# Custom_Sheild-PCB.net
KiCad netlist of a schematic drawn in EAGLE
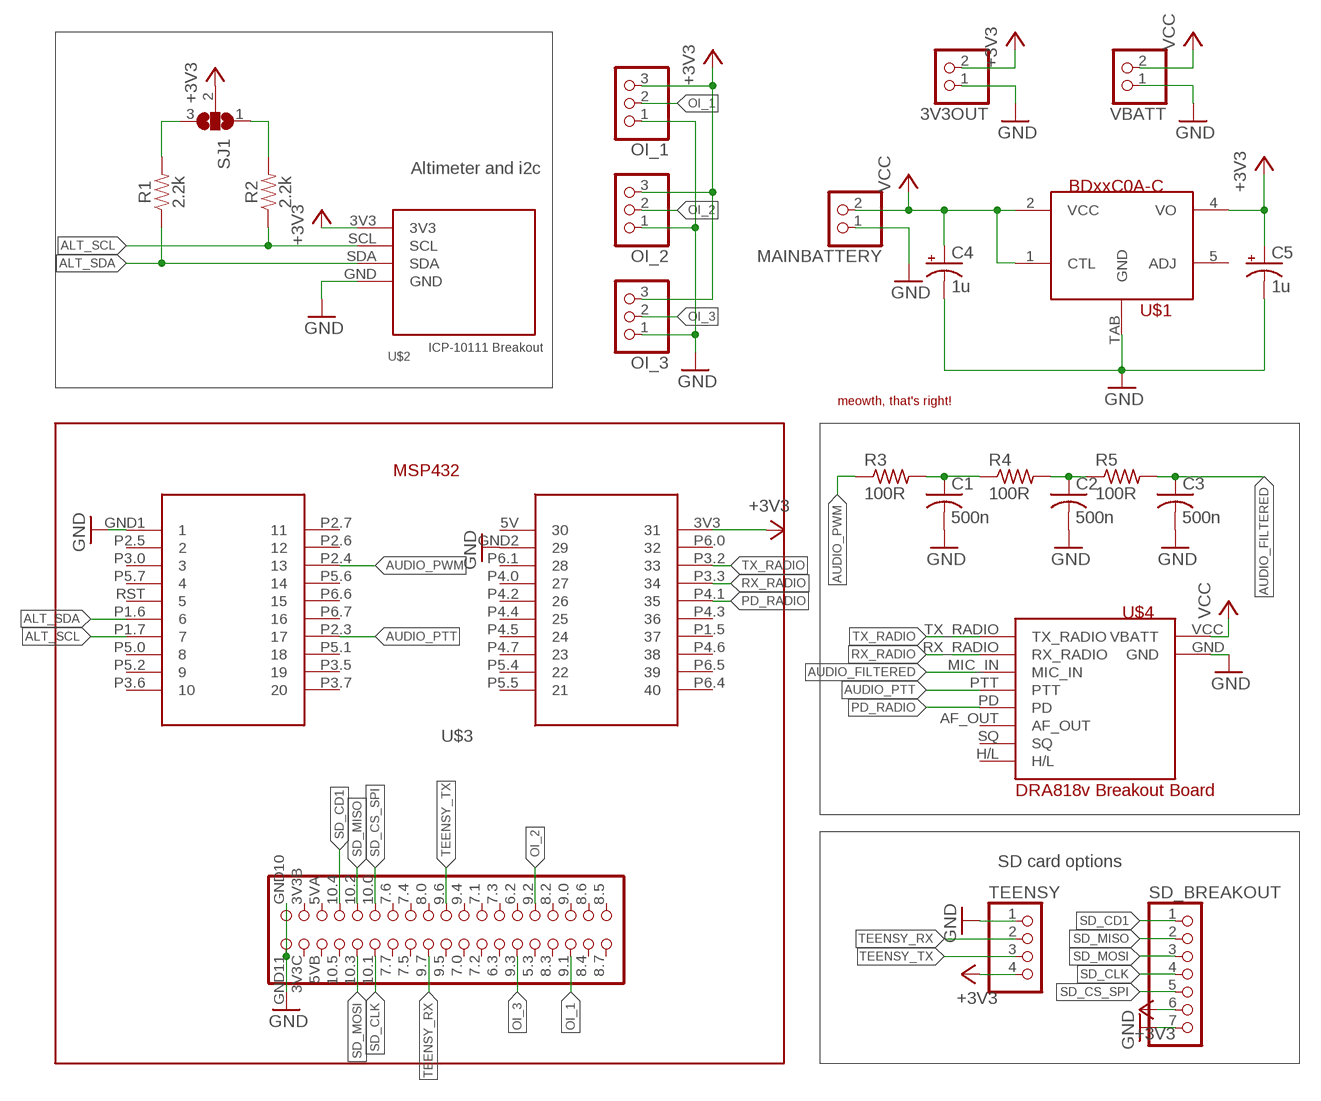
[diagram p0: schematic, sheet 1]

(export (version "E")
  (design (tool "Eeschema 10.0.6"))
  (components
    (comp (ref "3V3OUT")
      (value "PINHD-1X2")
      (footprint "eagle-import:1X02")
      (libsource (lib "eagle-import") (part "PINHD-1X2"))
    )
    (comp (ref "C1")
      (value "500n")
      (footprint "eagle-import:C0805")
      (libsource (lib "eagle-import") (part "C-USC0805"))
    )
    (comp (ref "C2")
      (value "500n")
      (footprint "eagle-import:C0805")
      (libsource (lib "eagle-import") (part "C-USC0805"))
    )
    (comp (ref "C3")
      (value "500n")
      (footprint "eagle-import:C0805")
      (libsource (lib "eagle-import") (part "C-USC0805"))
    )
    (comp (ref "C4")
      (value "1u")
      (footprint "eagle-import:PANASONIC_A")
      (libsource (lib "eagle-import") (part "CPOL-USA"))
    )
    (comp (ref "C5")
      (value "1u")
      (footprint "eagle-import:PANASONIC_A")
      (libsource (lib "eagle-import") (part "CPOL-USA"))
    )
    (comp (ref "MAINBATTERY")
      (value "PINHD-1X2")
      (footprint "eagle-import:1X02")
      (libsource (lib "eagle-import") (part "PINHD-1X2"))
    )
    (comp (ref "OI_1")
      (value "PINHD-1X3")
      (footprint "eagle-import:1X03")
      (libsource (lib "eagle-import") (part "PINHD-1X3"))
    )
    (comp (ref "OI_2")
      (value "PINHD-1X3")
      (footprint "eagle-import:1X03")
      (libsource (lib "eagle-import") (part "PINHD-1X3"))
    )
    (comp (ref "OI_3")
      (value "PINHD-1X3")
      (footprint "eagle-import:1X03")
      (libsource (lib "eagle-import") (part "PINHD-1X3"))
    )
    (comp (ref "R1")
      (value "2.2k")
      (footprint "eagle-import:0603")
      (libsource (lib "eagle-import") (part "2.2KOHM-0603-1/10W-1%"))
    )
    (comp (ref "R2")
      (value "2.2k")
      (footprint "eagle-import:0603")
      (libsource (lib "eagle-import") (part "2.2KOHM-0603-1/10W-1%"))
    )
    (comp (ref "R3")
      (value "100R")
      (footprint "eagle-import:R0805")
      (libsource (lib "eagle-import") (part "R-US_R0805"))
    )
    (comp (ref "R4")
      (value "100R")
      (footprint "eagle-import:R0805")
      (libsource (lib "eagle-import") (part "R-US_R0805"))
    )
    (comp (ref "R5")
      (value "100R")
      (footprint "eagle-import:R0805")
      (libsource (lib "eagle-import") (part "R-US_R0805"))
    )
    (comp (ref "SD_BREAKOUT")
      (value "PINHD-1X7")
      (footprint "eagle-import:1X07")
      (libsource (lib "eagle-import") (part "PINHD-1X7"))
    )
    (comp (ref "SJ1")
      (value "SJ2W")
      (footprint "eagle-import:SJ_2")
      (libsource (lib "eagle-import") (part "SJ2W"))
    )
    (comp (ref "TEENSY")
      (value "PINHD-1X4")
      (footprint "eagle-import:1X04")
      (libsource (lib "eagle-import") (part "PINHD-1X4"))
    )
    (comp (ref "U$1")
      (value "BDXXC0A-CBD33C0AWFP-CE2")
      (footprint "eagle-import:TO252-5-11")
      (libsource (lib "eagle-import") (part "BDXXC0A-CBD33C0AWFP-CE2"))
    )
    (comp (ref "U$2")
      (value "ALTIMETER")
      (footprint "eagle-import:ALTIMETER")
      (libsource (lib "eagle-import") (part "ALTIMETER"))
    )
    (comp (ref "U$3")
      (value "MSP432")
      (footprint "eagle-import:MSP432")
      (libsource (lib "eagle-import") (part "MSP432"))
    )
    (comp (ref "U$4")
      (value "DRA_BREAKOUT")
      (footprint "eagle-import:DRA_BREAKOUT")
      (libsource (lib "eagle-import") (part "DRA_BREAKOUT"))
    )
    (comp (ref "U$5")
      (value "MEOWTH")
      (footprint "eagle-import:MEOWTH")
      (libsource (lib "eagle-import") (part "MEOWTH"))
    )
    (comp (ref "VBATT")
      (value "PINHD-1X2")
      (footprint "eagle-import:1X02")
      (libsource (lib "eagle-import") (part "PINHD-1X2"))
    )
  )
  (nets
    (net (code "1") (name "+3V3") (class "Default")
      (node (ref "3V3OUT") (pin "2") (pinfunction "2_2") (pintype "passive"))
      (node (ref "C5") (pin "+") (pinfunction "+_+") (pintype "passive"))
      (node (ref "OI_1") (pin "3") (pinfunction "3_3") (pintype "passive"))
      (node (ref "OI_2") (pin "3") (pinfunction "3_3") (pintype "passive"))
      (node (ref "OI_3") (pin "3") (pinfunction "3_3") (pintype "passive"))
      (node (ref "SD_BREAKOUT") (pin "6") (pinfunction "6_6") (pintype "passive"))
      (node (ref "SJ1") (pin "2") (pinfunction "2_2") (pintype "passive"))
      (node (ref "TEENSY") (pin "4") (pinfunction "4_4") (pintype "passive"))
      (node (ref "U$1") (pin "4") (pinfunction "VO_4") (pintype "power_in"))
      (node (ref "U$2") (pin "3V3") (pinfunction "3V3_3V3") (pintype "power_in"))
      (node (ref "U$3") (pin "3V3") (pinfunction "31_3V3") (pintype "power_in"))
    )
    (net (code "2") (name "/30") (class "Default")
      (node (ref "U$3") (pin "5V") (pinfunction "30_5V") (pintype "power_in"))
    )
    (net (code "3") (name "ALT_SCL") (class "Default")
      (node (ref "R2") (pin "1") (pinfunction "1_1") (pintype "passive"))
      (node (ref "U$2") (pin "SCL") (pinfunction "SCL_SCL") (pintype "bidirectional"))
      (node (ref "U$3") (pin "P1.7") (pinfunction "7_P1.7") (pintype "bidirectional"))
    )
    (net (code "4") (name "ALT_SDA") (class "Default")
      (node (ref "R1") (pin "1") (pinfunction "1_1") (pintype "passive"))
      (node (ref "U$2") (pin "SDA") (pinfunction "SDA_SDA") (pintype "bidirectional"))
      (node (ref "U$3") (pin "P1.6") (pinfunction "6_P1.6") (pintype "bidirectional"))
    )
    (net (code "5") (name "AUDIO_FILTERED") (class "Default")
      (node (ref "C3") (pin "1") (pinfunction "1_1") (pintype "passive"))
      (node (ref "R5") (pin "2") (pinfunction "2_2") (pintype "passive"))
      (node (ref "U$4") (pin "MIC_IN") (pinfunction "MIC_IN_MIC_IN") (pintype "bidirectional"))
    )
    (net (code "6") (name "AUDIO_PTT") (class "Default")
      (node (ref "U$3") (pin "P2.3") (pinfunction "17_P2.3") (pintype "bidirectional"))
      (node (ref "U$4") (pin "PTT") (pinfunction "PTT_PTT") (pintype "bidirectional"))
    )
    (net (code "7") (name "AUDIO_PWM") (class "Default")
      (node (ref "R3") (pin "1") (pinfunction "1_1") (pintype "passive"))
      (node (ref "U$3") (pin "P2.4") (pinfunction "13_P2.4") (pintype "bidirectional"))
    )
    (net (code "8") (name "GND") (class "Default")
      (node (ref "3V3OUT") (pin "1") (pinfunction "1_1") (pintype "passive"))
      (node (ref "C1") (pin "2") (pinfunction "2_2") (pintype "passive"))
      (node (ref "C2") (pin "2") (pinfunction "2_2") (pintype "passive"))
      (node (ref "C3") (pin "2") (pinfunction "2_2") (pintype "passive"))
      (node (ref "C4") (pin "-") (pinfunction "-_-") (pintype "passive"))
      (node (ref "C5") (pin "-") (pinfunction "-_-") (pintype "passive"))
      (node (ref "MAINBATTERY") (pin "1") (pinfunction "1_1") (pintype "passive"))
      (node (ref "OI_1") (pin "1") (pinfunction "1_1") (pintype "passive"))
      (node (ref "OI_2") (pin "1") (pinfunction "1_1") (pintype "passive"))
      (node (ref "OI_3") (pin "1") (pinfunction "1_1") (pintype "passive"))
      (node (ref "SD_BREAKOUT") (pin "7") (pinfunction "7_7") (pintype "passive"))
      (node (ref "TEENSY") (pin "1") (pinfunction "1_1") (pintype "passive"))
      (node (ref "U$1") (pin "TAB") (pinfunction "GND_TAB") (pintype "bidirectional"))
      (node (ref "U$2") (pin "GND") (pinfunction "GND_GND") (pintype "power_in"))
      (node (ref "U$3") (pin "GND1") (pinfunction "1_GND1") (pintype "power_in"))
      (node (ref "U$3") (pin "GND10") (pinfunction "42_GND10") (pintype "passive"))
      (node (ref "U$3") (pin "GND11") (pinfunction "41_GND11") (pintype "passive"))
      (node (ref "U$3") (pin "GND2") (pinfunction "29_GND2") (pintype "power_in"))
      (node (ref "U$4") (pin "GND") (pinfunction "GND_GND") (pintype "power_in"))
      (node (ref "VBATT") (pin "1") (pinfunction "1_1") (pintype "passive"))
    )
    (net (code "9") (name "Net-(C1-Pad1)") (class "Default")
      (node (ref "C1") (pin "1") (pinfunction "1_1") (pintype "passive"))
      (node (ref "R3") (pin "2") (pinfunction "2_2") (pintype "passive"))
      (node (ref "R4") (pin "1") (pinfunction "1_1") (pintype "passive"))
    )
    (net (code "10") (name "Net-(C2-Pad1)") (class "Default")
      (node (ref "C2") (pin "1") (pinfunction "1_1") (pintype "passive"))
      (node (ref "R4") (pin "2") (pinfunction "2_2") (pintype "passive"))
      (node (ref "R5") (pin "1") (pinfunction "1_1") (pintype "passive"))
    )
    (net (code "11") (name "Net-(R1-Pad2)") (class "Default")
      (node (ref "R1") (pin "2") (pinfunction "2_2") (pintype "passive"))
      (node (ref "SJ1") (pin "3") (pinfunction "3_3") (pintype "passive"))
    )
    (net (code "12") (name "Net-(R2-Pad2)") (class "Default")
      (node (ref "R2") (pin "2") (pinfunction "2_2") (pintype "passive"))
      (node (ref "SJ1") (pin "1") (pinfunction "1_1") (pintype "passive"))
    )
    (net (code "13") (name "OI_1") (class "Default")
      (node (ref "OI_1") (pin "2") (pinfunction "2_2") (pintype "passive"))
      (node (ref "U$3") (pin "9.1") (pinfunction "73_9.1") (pintype "passive"))
    )
    (net (code "14") (name "OI_2") (class "Default")
      (node (ref "OI_2") (pin "2") (pinfunction "2_2") (pintype "passive"))
      (node (ref "U$3") (pin "9.2") (pinfunction "70_9.2") (pintype "passive"))
    )
    (net (code "15") (name "OI_3") (class "Default")
      (node (ref "OI_3") (pin "2") (pinfunction "2_2") (pintype "passive"))
      (node (ref "U$3") (pin "9.3") (pinfunction "67_9.3") (pintype "passive"))
    )
    (net (code "16") (name "PD_RADIO") (class "Default")
      (node (ref "U$3") (pin "P4.1") (pinfunction "35_P4.1") (pintype "bidirectional"))
      (node (ref "U$4") (pin "PD") (pinfunction "PD_PD") (pintype "bidirectional"))
    )
    (net (code "17") (name "RX_RADIO") (class "Default")
      (node (ref "U$3") (pin "P3.3") (pinfunction "34_P3.3") (pintype "bidirectional"))
      (node (ref "U$4") (pin "RX_RADIO") (pinfunction "RX_RADIO_RX_RADIO") (pintype "bidirectional"))
    )
    (net (code "18") (name "SD_CD1") (class "Default")
      (node (ref "SD_BREAKOUT") (pin "1") (pinfunction "1_1") (pintype "passive"))
      (node (ref "U$3") (pin "10.4") (pinfunction "48_10.4") (pintype "passive"))
    )
    (net (code "19") (name "SD_CLK") (class "Default")
      (node (ref "SD_BREAKOUT") (pin "4") (pinfunction "4_4") (pintype "passive"))
      (node (ref "U$3") (pin "10.1") (pinfunction "51_10.1") (pintype "passive"))
    )
    (net (code "20") (name "SD_CS_SPI") (class "Default")
      (node (ref "SD_BREAKOUT") (pin "5") (pinfunction "5_5") (pintype "passive"))
      (node (ref "U$3") (pin "10.0") (pinfunction "52_10.0") (pintype "passive"))
    )
    (net (code "21") (name "SD_MISO") (class "Default")
      (node (ref "SD_BREAKOUT") (pin "2") (pinfunction "2_2") (pintype "passive"))
      (node (ref "U$3") (pin "10.2") (pinfunction "50_10.2") (pintype "passive"))
    )
    (net (code "22") (name "SD_MOSI") (class "Default")
      (node (ref "SD_BREAKOUT") (pin "3") (pinfunction "3_3") (pintype "passive"))
      (node (ref "U$3") (pin "10.3") (pinfunction "49_10.3") (pintype "passive"))
    )
    (net (code "23") (name "TEENSY_RX") (class "Default")
      (node (ref "TEENSY") (pin "2") (pinfunction "2_2") (pintype "passive"))
      (node (ref "U$3") (pin "9.7") (pinfunction "57_9.7") (pintype "passive"))
    )
    (net (code "24") (name "TEENSY_TX") (class "Default")
      (node (ref "TEENSY") (pin "3") (pinfunction "3_3") (pintype "passive"))
      (node (ref "U$3") (pin "9.6") (pinfunction "60_9.6") (pintype "passive"))
    )
    (net (code "25") (name "TX_RADIO") (class "Default")
      (node (ref "U$3") (pin "P3.2") (pinfunction "33_P3.2") (pintype "bidirectional"))
      (node (ref "U$4") (pin "TX_RADIO") (pinfunction "TX_RADIO_TX_RADIO") (pintype "bidirectional"))
    )
    (net (code "26") (name "VCC") (class "Default")
      (node (ref "C4") (pin "+") (pinfunction "+_+") (pintype "passive"))
      (node (ref "MAINBATTERY") (pin "2") (pinfunction "2_2") (pintype "passive"))
      (node (ref "U$1") (pin "1") (pinfunction "CTL_1") (pintype "bidirectional"))
      (node (ref "U$1") (pin "2") (pinfunction "VCC_2") (pintype "power_in"))
      (node (ref "U$4") (pin "VCC") (pinfunction "VBATT_VCC") (pintype "power_in"))
      (node (ref "VBATT") (pin "2") (pinfunction "2_2") (pintype "passive"))
    )
    (net (code "27") (name "unconnected-(U$1-ADJ-Pad5)") (class "Default")
      (node (ref "U$1") (pin "5") (pinfunction "ADJ_5") (pintype "bidirectional"))
    )
    (net (code "28") (name "unconnected-(U$3-2-PadP2.5)") (class "Default")
      (node (ref "U$3") (pin "P2.5") (pinfunction "2_P2.5") (pintype "bidirectional"))
    )
    (net (code "29") (name "unconnected-(U$3-3-PadP3.0)") (class "Default")
      (node (ref "U$3") (pin "P3.0") (pinfunction "3_P3.0") (pintype "bidirectional"))
    )
    (net (code "30") (name "unconnected-(U$3-4-PadP5.7)") (class "Default")
      (node (ref "U$3") (pin "P5.7") (pinfunction "4_P5.7") (pintype "bidirectional"))
    )
    (net (code "31") (name "unconnected-(U$3-5-PadRST)") (class "Default")
      (node (ref "U$3") (pin "RST") (pinfunction "5_RST") (pintype "bidirectional"))
    )
    (net (code "32") (name "unconnected-(U$3-8-PadP5.0)") (class "Default")
      (node (ref "U$3") (pin "P5.0") (pinfunction "8_P5.0") (pintype "bidirectional"))
    )
    (net (code "33") (name "unconnected-(U$3-9-PadP5.2)") (class "Default")
      (node (ref "U$3") (pin "P5.2") (pinfunction "9_P5.2") (pintype "bidirectional"))
    )
    (net (code "34") (name "unconnected-(U$3-10-PadP3.6)") (class "Default")
      (node (ref "U$3") (pin "P3.6") (pinfunction "10_P3.6") (pintype "bidirectional"))
    )
    (net (code "35") (name "unconnected-(U$3-11-PadP2.7)") (class "Default")
      (node (ref "U$3") (pin "P2.7") (pinfunction "11_P2.7") (pintype "bidirectional"))
    )
    (net (code "36") (name "unconnected-(U$3-12-PadP2.6)") (class "Default")
      (node (ref "U$3") (pin "P2.6") (pinfunction "12_P2.6") (pintype "bidirectional"))
    )
    (net (code "37") (name "unconnected-(U$3-14-PadP5.6)") (class "Default")
      (node (ref "U$3") (pin "P5.6") (pinfunction "14_P5.6") (pintype "bidirectional"))
    )
    (net (code "38") (name "unconnected-(U$3-15-PadP6.6)") (class "Default")
      (node (ref "U$3") (pin "P6.6") (pinfunction "15_P6.6") (pintype "bidirectional"))
    )
    (net (code "39") (name "unconnected-(U$3-16-PadP6.7)") (class "Default")
      (node (ref "U$3") (pin "P6.7") (pinfunction "16_P6.7") (pintype "bidirectional"))
    )
    (net (code "40") (name "unconnected-(U$3-18-PadP5.1)") (class "Default")
      (node (ref "U$3") (pin "P5.1") (pinfunction "18_P5.1") (pintype "bidirectional"))
    )
    (net (code "41") (name "unconnected-(U$3-19-PadP3.5)") (class "Default")
      (node (ref "U$3") (pin "P3.5") (pinfunction "19_P3.5") (pintype "bidirectional"))
    )
    (net (code "42") (name "unconnected-(U$3-20-PadP3.7)") (class "Default")
      (node (ref "U$3") (pin "P3.7") (pinfunction "20_P3.7") (pintype "bidirectional"))
    )
    (net (code "43") (name "unconnected-(U$3-21-PadP5.5)") (class "Default")
      (node (ref "U$3") (pin "P5.5") (pinfunction "21_P5.5") (pintype "bidirectional"))
    )
    (net (code "44") (name "unconnected-(U$3-22-PadP5.4)") (class "Default")
      (node (ref "U$3") (pin "P5.4") (pinfunction "22_P5.4") (pintype "bidirectional"))
    )
    (net (code "45") (name "unconnected-(U$3-23-PadP4.7)") (class "Default")
      (node (ref "U$3") (pin "P4.7") (pinfunction "23_P4.7") (pintype "bidirectional"))
    )
    (net (code "46") (name "unconnected-(U$3-24-PadP4.5)") (class "Default")
      (node (ref "U$3") (pin "P4.5") (pinfunction "24_P4.5") (pintype "bidirectional"))
    )
    (net (code "47") (name "unconnected-(U$3-25-PadP4.4)") (class "Default")
      (node (ref "U$3") (pin "P4.4") (pinfunction "25_P4.4") (pintype "bidirectional"))
    )
    (net (code "48") (name "unconnected-(U$3-26-PadP4.2)") (class "Default")
      (node (ref "U$3") (pin "P4.2") (pinfunction "26_P4.2") (pintype "bidirectional"))
    )
    (net (code "49") (name "unconnected-(U$3-27-PadP4.0)") (class "Default")
      (node (ref "U$3") (pin "P4.0") (pinfunction "27_P4.0") (pintype "bidirectional"))
    )
    (net (code "50") (name "unconnected-(U$3-28-PadP6.1)") (class "Default")
      (node (ref "U$3") (pin "P6.1") (pinfunction "28_P6.1") (pintype "bidirectional"))
    )
    (net (code "51") (name "unconnected-(U$3-32-PadP6.0)") (class "Default")
      (node (ref "U$3") (pin "P6.0") (pinfunction "32_P6.0") (pintype "bidirectional"))
    )
    (net (code "52") (name "unconnected-(U$3-36-PadP4.3)") (class "Default")
      (node (ref "U$3") (pin "P4.3") (pinfunction "36_P4.3") (pintype "bidirectional"))
    )
    (net (code "53") (name "unconnected-(U$3-37-PadP1.5)") (class "Default")
      (node (ref "U$3") (pin "P1.5") (pinfunction "37_P1.5") (pintype "bidirectional"))
    )
    (net (code "54") (name "unconnected-(U$3-38-PadP4.6)") (class "Default")
      (node (ref "U$3") (pin "P4.6") (pinfunction "38_P4.6") (pintype "bidirectional"))
    )
    (net (code "55") (name "unconnected-(U$3-39-PadP6.5)") (class "Default")
      (node (ref "U$3") (pin "P6.5") (pinfunction "39_P6.5") (pintype "bidirectional"))
    )
    (net (code "56") (name "unconnected-(U$3-40-PadP6.4)") (class "Default")
      (node (ref "U$3") (pin "P6.4") (pinfunction "40_P6.4") (pintype "bidirectional"))
    )
    (net (code "57") (name "unconnected-(U$3-43-Pad3V3C)") (class "Default")
      (node (ref "U$3") (pin "3V3C") (pinfunction "43_3V3C") (pintype "passive"))
    )
    (net (code "58") (name "unconnected-(U$3-44-Pad3V3B)") (class "Default")
      (node (ref "U$3") (pin "3V3B") (pinfunction "44_3V3B") (pintype "passive"))
    )
    (net (code "59") (name "unconnected-(U$3-45-Pad5VB)") (class "Default")
      (node (ref "U$3") (pin "5VB") (pinfunction "45_5VB") (pintype "passive"))
    )
    (net (code "60") (name "unconnected-(U$3-46-Pad5VA)") (class "Default")
      (node (ref "U$3") (pin "5VA") (pinfunction "46_5VA") (pintype "passive"))
    )
    (net (code "61") (name "unconnected-(U$3-47-Pad10.5)") (class "Default")
      (node (ref "U$3") (pin "10.5") (pinfunction "47_10.5") (pintype "passive"))
    )
    (net (code "62") (name "unconnected-(U$3-53-Pad7.7)") (class "Default")
      (node (ref "U$3") (pin "7.7") (pinfunction "53_7.7") (pintype "passive"))
    )
    (net (code "63") (name "unconnected-(U$3-54-Pad7.6)") (class "Default")
      (node (ref "U$3") (pin "7.6") (pinfunction "54_7.6") (pintype "passive"))
    )
    (net (code "64") (name "unconnected-(U$3-55-Pad7.5)") (class "Default")
      (node (ref "U$3") (pin "7.5") (pinfunction "55_7.5") (pintype "passive"))
    )
    (net (code "65") (name "unconnected-(U$3-56-Pad7.4)") (class "Default")
      (node (ref "U$3") (pin "7.4") (pinfunction "56_7.4") (pintype "passive"))
    )
    (net (code "66") (name "unconnected-(U$3-58-Pad8.0)") (class "Default")
      (node (ref "U$3") (pin "8.0") (pinfunction "58_8.0") (pintype "passive"))
    )
    (net (code "67") (name "unconnected-(U$3-59-Pad9.5)") (class "Default")
      (node (ref "U$3") (pin "9.5") (pinfunction "59_9.5") (pintype "passive"))
    )
    (net (code "68") (name "unconnected-(U$3-61-Pad7.0)") (class "Default")
      (node (ref "U$3") (pin "7.0") (pinfunction "61_7.0") (pintype "passive"))
    )
    (net (code "69") (name "unconnected-(U$3-62-Pad9.4)") (class "Default")
      (node (ref "U$3") (pin "9.4") (pinfunction "62_9.4") (pintype "passive"))
    )
    (net (code "70") (name "unconnected-(U$3-63-Pad7.2)") (class "Default")
      (node (ref "U$3") (pin "7.2") (pinfunction "63_7.2") (pintype "passive"))
    )
    (net (code "71") (name "unconnected-(U$3-64-Pad7.1)") (class "Default")
      (node (ref "U$3") (pin "7.1") (pinfunction "64_7.1") (pintype "passive"))
    )
    (net (code "72") (name "unconnected-(U$3-65-Pad6.3)") (class "Default")
      (node (ref "U$3") (pin "6.3") (pinfunction "65_6.3") (pintype "passive"))
    )
    (net (code "73") (name "unconnected-(U$3-66-Pad7.3)") (class "Default")
      (node (ref "U$3") (pin "7.3") (pinfunction "66_7.3") (pintype "passive"))
    )
    (net (code "74") (name "unconnected-(U$3-68-Pad6.2)") (class "Default")
      (node (ref "U$3") (pin "6.2") (pinfunction "68_6.2") (pintype "passive"))
    )
    (net (code "75") (name "unconnected-(U$3-69-Pad5.3)") (class "Default")
      (node (ref "U$3") (pin "5.3") (pinfunction "69_5.3") (pintype "passive"))
    )
    (net (code "76") (name "unconnected-(U$3-71-Pad8.3)") (class "Default")
      (node (ref "U$3") (pin "8.3") (pinfunction "71_8.3") (pintype "passive"))
    )
    (net (code "77") (name "unconnected-(U$3-72-Pad8.2)") (class "Default")
      (node (ref "U$3") (pin "8.2") (pinfunction "72_8.2") (pintype "passive"))
    )
    (net (code "78") (name "unconnected-(U$3-74-Pad8.4)") (class "Default")
      (node (ref "U$3") (pin "8.4") (pinfunction "74_8.4") (pintype "passive"))
    )
    (net (code "79") (name "unconnected-(U$3-75-Pad8.7)") (class "Default")
      (node (ref "U$3") (pin "8.7") (pinfunction "75_8.7") (pintype "passive"))
    )
    (net (code "80") (name "unconnected-(U$3-76-Pad9.0)") (class "Default")
      (node (ref "U$3") (pin "9.0") (pinfunction "76_9.0") (pintype "passive"))
    )
    (net (code "81") (name "unconnected-(U$3-77-Pad8.6)") (class "Default")
      (node (ref "U$3") (pin "8.6") (pinfunction "77_8.6") (pintype "passive"))
    )
    (net (code "82") (name "unconnected-(U$3-78-Pad8.5)") (class "Default")
      (node (ref "U$3") (pin "8.5") (pinfunction "78_8.5") (pintype "passive"))
    )
    (net (code "83") (name "unconnected-(U$4-PadAF_OUT)") (class "Default")
      (node (ref "U$4") (pin "AF_OUT") (pinfunction "AF_OUT_AF_OUT") (pintype "bidirectional"))
    )
    (net (code "84") (name "unconnected-(U$4-PadH{slash}L)") (class "Default")
      (node (ref "U$4") (pin "H/L") (pinfunction "H/L_H/L") (pintype "bidirectional"))
    )
    (net (code "85") (name "unconnected-(U$4-PadSQ)") (class "Default")
      (node (ref "U$4") (pin "SQ") (pinfunction "SQ_SQ") (pintype "bidirectional"))
    )
  )
)
